# I2C_Switch_temp_sens.net
KiCad netlist of a schematic drawn in Altium Designer
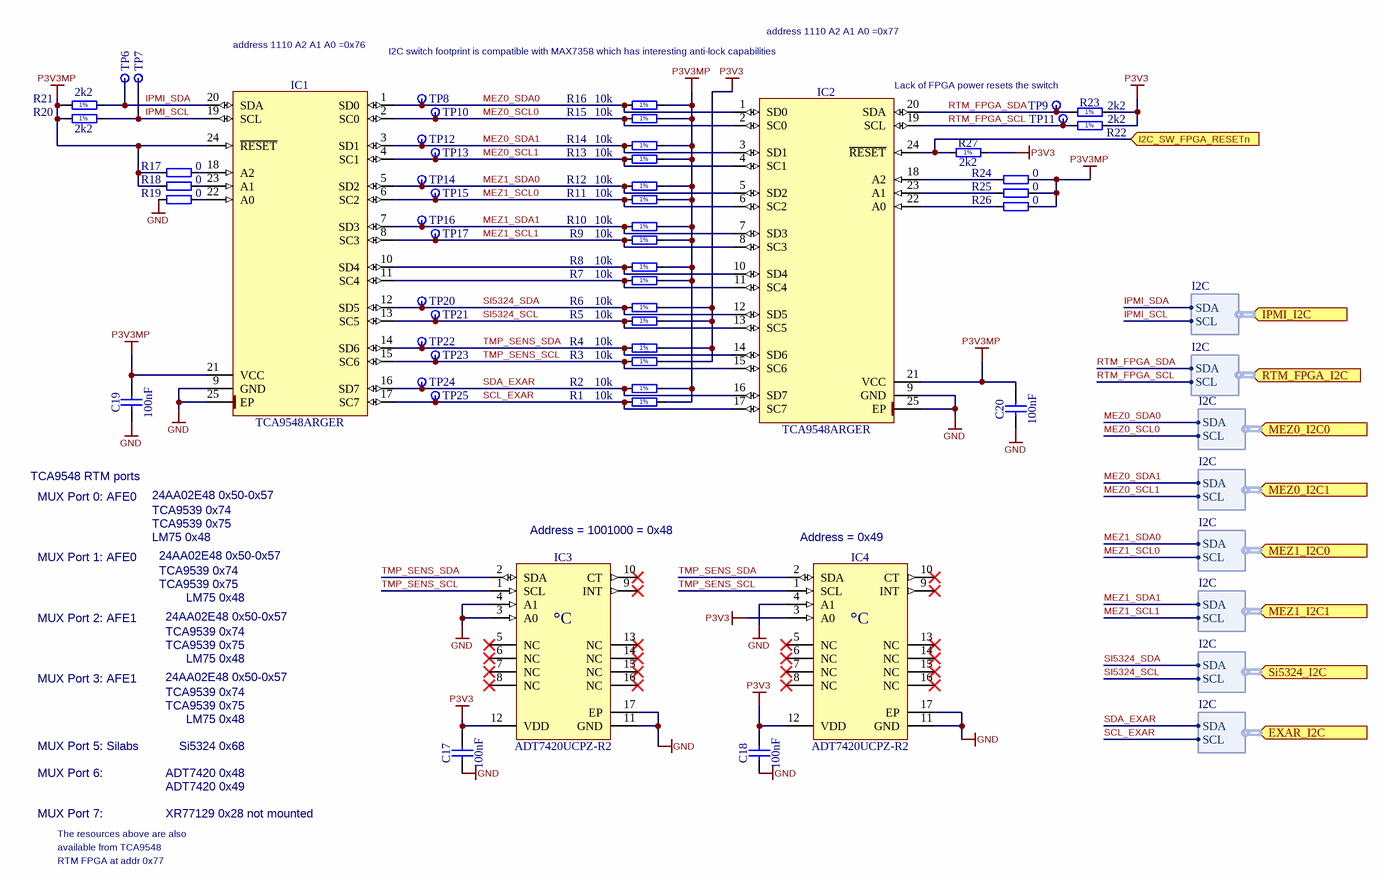
[diagram p0: I2C_Switch_temp_sens.SchDoc]

(export (version "E")
  (design (tool "Eeschema 10.0.6"))
  (components
    (comp (ref "C17")
      (value "100nF")
      (footprint "CAPC0603X33N")
      (description "Non-polarised capacitor")
      (fields
        (field (name "MANUFACTURER PART NUMBER") "CC0201_100NF_6.3V_10%_X5R")
        (field (name "MANUFACTURER") "GENERIC")
        (field (name "AUTHOR") "CERN DEM JLC")
      )
      (libsource (lib "Capacitors") (part "Capacitor - non polarized"))
    )
    (comp (ref "C18")
      (value "100nF")
      (footprint "CAPC0603X33N")
      (description "Non-polarised capacitor")
      (fields
        (field (name "MANUFACTURER PART NUMBER") "CC0201_100NF_6.3V_10%_X5R")
        (field (name "MANUFACTURER") "GENERIC")
        (field (name "AUTHOR") "CERN DEM JLC")
      )
      (libsource (lib "Capacitors") (part "Capacitor - non polarized"))
    )
    (comp (ref "C19")
      (value "100nF")
      (footprint "CAPC0603X33N")
      (description "Non-polarised capacitor")
      (fields
        (field (name "MANUFACTURER PART NUMBER") "CC0201_100NF_6.3V_10%_X5R")
        (field (name "MANUFACTURER") "GENERIC")
        (field (name "AUTHOR") "CERN DEM JLC")
      )
      (libsource (lib "Capacitors") (part "Capacitor - non polarized"))
    )
    (comp (ref "C20")
      (value "100nF")
      (footprint "CAPC0603X33N")
      (description "Non-polarised capacitor")
      (fields
        (field (name "MANUFACTURER PART NUMBER") "CC0201_100NF_6.3V_10%_X5R")
        (field (name "MANUFACTURER") "GENERIC")
        (field (name "AUTHOR") "CERN DEM JLC")
      )
      (libsource (lib "Capacitors") (part "Capacitor - non polarized"))
    )
    (comp (ref "IC1")
      (value "TCA9548ARGER")
      (footprint "QFN50P400X400X100-25N-S220")
      (description "Low Voltage 8-Channel I2C Switch With Reset")
      (fields (field (name "MANUFACTURER") "TEXAS INSTRUMENTS") (field (name "AUTHOR") "CERN DEM JLC"))
      (libsource (lib "ICs And Semiconductors") (part "TCA9548ARGER"))
    )
    (comp (ref "IC2")
      (value "TCA9548ARGER")
      (footprint "QFN50P400X400X100-25N-S220")
      (description "Low Voltage 8-Channel I2C Switch With Reset")
      (fields (field (name "MANUFACTURER") "TEXAS INSTRUMENTS") (field (name "AUTHOR") "CERN DEM JLC"))
      (libsource (lib "") (part "TCA9548ARGER_1"))
    )
    (comp (ref "IC3")
      (value "ADT7420UCPZ-R2")
      (footprint "QFN65P400X400X80-17N-S270")
      (description "±0.25°C Accurate, 16-Bit Digital I2C Temperature Sensor")
      (fields (field (name "MANUFACTURER") "ANALOG DEVICES") (field (name "AUTHOR") "CERN DEM JLC"))
      (libsource (lib "ICs And Semiconductors") (part "ADT7420"))
    )
    (comp (ref "IC4")
      (value "ADT7420UCPZ-R2")
      (footprint "QFN65P400X400X80-17N-S270")
      (description "±0.25°C Accurate, 16-Bit Digital I2C Temperature Sensor")
      (fields (field (name "MANUFACTURER") "ANALOG DEVICES") (field (name "AUTHOR") "CERN DEM JLC"))
      (libsource (lib "ICs And Semiconductors") (part "ADT7420"))
    )
    (comp (ref "R1")
      (value "10k")
      (footprint "RESC1005X40N")
      (description "Resistor - 1%")
      (fields
        (field (name "MANUFACTURER PART NUMBER") "R0402_10K_1%_0.0625W_100PPM")
        (field (name "MANUFACTURER") "GENERIC")
        (field (name "AUTHOR") "CERN DEM JLC")
      )
      (libsource (lib "Resistors") (part "Resistor - 1%"))
    )
    (comp (ref "R2")
      (value "10k")
      (footprint "RESC1005X40N")
      (description "Resistor - 1%")
      (fields
        (field (name "MANUFACTURER PART NUMBER") "R0402_10K_1%_0.0625W_100PPM")
        (field (name "MANUFACTURER") "GENERIC")
        (field (name "AUTHOR") "CERN DEM JLC")
      )
      (libsource (lib "Resistors") (part "Resistor - 1%"))
    )
    (comp (ref "R3")
      (value "10k")
      (footprint "RESC1005X40N")
      (description "Resistor - 1%")
      (fields
        (field (name "MANUFACTURER PART NUMBER") "R0402_10K_1%_0.0625W_100PPM")
        (field (name "MANUFACTURER") "GENERIC")
        (field (name "AUTHOR") "CERN DEM JLC")
      )
      (libsource (lib "Resistors") (part "Resistor - 1%"))
    )
    (comp (ref "R4")
      (value "10k")
      (footprint "RESC1005X40N")
      (description "Resistor - 1%")
      (fields
        (field (name "MANUFACTURER PART NUMBER") "R0402_10K_1%_0.0625W_100PPM")
        (field (name "MANUFACTURER") "GENERIC")
        (field (name "AUTHOR") "CERN DEM JLC")
      )
      (libsource (lib "Resistors") (part "Resistor - 1%"))
    )
    (comp (ref "R5")
      (value "10k")
      (footprint "RESC1005X40N")
      (description "Resistor - 1%")
      (fields
        (field (name "MANUFACTURER PART NUMBER") "R0402_10K_1%_0.0625W_100PPM")
        (field (name "MANUFACTURER") "GENERIC")
        (field (name "AUTHOR") "CERN DEM JLC")
      )
      (libsource (lib "Resistors") (part "Resistor - 1%"))
    )
    (comp (ref "R6")
      (value "10k")
      (footprint "RESC1005X40N")
      (description "Resistor - 1%")
      (fields
        (field (name "MANUFACTURER PART NUMBER") "R0402_10K_1%_0.0625W_100PPM")
        (field (name "MANUFACTURER") "GENERIC")
        (field (name "AUTHOR") "CERN DEM JLC")
      )
      (libsource (lib "Resistors") (part "Resistor - 1%"))
    )
    (comp (ref "R7")
      (value "10k")
      (footprint "RESC1005X40N")
      (description "Resistor - 1%")
      (fields
        (field (name "MANUFACTURER PART NUMBER") "R0402_10K_1%_0.0625W_100PPM")
        (field (name "MANUFACTURER") "GENERIC")
        (field (name "AUTHOR") "CERN DEM JLC")
      )
      (libsource (lib "Resistors") (part "Resistor - 1%"))
    )
    (comp (ref "R8")
      (value "10k")
      (footprint "RESC1005X40N")
      (description "Resistor - 1%")
      (fields
        (field (name "MANUFACTURER PART NUMBER") "R0402_10K_1%_0.0625W_100PPM")
        (field (name "MANUFACTURER") "GENERIC")
        (field (name "AUTHOR") "CERN DEM JLC")
      )
      (libsource (lib "Resistors") (part "Resistor - 1%"))
    )
    (comp (ref "R9")
      (value "10k")
      (footprint "RESC1005X40N")
      (description "Resistor - 1%")
      (fields
        (field (name "MANUFACTURER PART NUMBER") "R0402_10K_1%_0.0625W_100PPM")
        (field (name "MANUFACTURER") "GENERIC")
        (field (name "AUTHOR") "CERN DEM JLC")
      )
      (libsource (lib "Resistors") (part "Resistor - 1%"))
    )
    (comp (ref "R10")
      (value "10k")
      (footprint "RESC1005X40N")
      (description "Resistor - 1%")
      (fields
        (field (name "MANUFACTURER PART NUMBER") "R0402_10K_1%_0.0625W_100PPM")
        (field (name "MANUFACTURER") "GENERIC")
        (field (name "AUTHOR") "CERN DEM JLC")
      )
      (libsource (lib "Resistors") (part "Resistor - 1%"))
    )
    (comp (ref "R11")
      (value "10k")
      (footprint "RESC1005X40N")
      (description "Resistor - 1%")
      (fields
        (field (name "MANUFACTURER PART NUMBER") "R0402_10K_1%_0.0625W_100PPM")
        (field (name "MANUFACTURER") "GENERIC")
        (field (name "AUTHOR") "CERN DEM JLC")
      )
      (libsource (lib "Resistors") (part "Resistor - 1%"))
    )
    (comp (ref "R12")
      (value "10k")
      (footprint "RESC1005X40N")
      (description "Resistor - 1%")
      (fields
        (field (name "MANUFACTURER PART NUMBER") "R0402_10K_1%_0.0625W_100PPM")
        (field (name "MANUFACTURER") "GENERIC")
        (field (name "AUTHOR") "CERN DEM JLC")
      )
      (libsource (lib "Resistors") (part "Resistor - 1%"))
    )
    (comp (ref "R13")
      (value "10k")
      (footprint "RESC1005X40N")
      (description "Resistor - 1%")
      (fields
        (field (name "MANUFACTURER PART NUMBER") "R0402_10K_1%_0.0625W_100PPM")
        (field (name "MANUFACTURER") "GENERIC")
        (field (name "AUTHOR") "CERN DEM JLC")
      )
      (libsource (lib "Resistors") (part "Resistor - 1%"))
    )
    (comp (ref "R14")
      (value "10k")
      (footprint "RESC1005X40N")
      (description "Resistor - 1%")
      (fields
        (field (name "MANUFACTURER PART NUMBER") "R0402_10K_1%_0.0625W_100PPM")
        (field (name "MANUFACTURER") "GENERIC")
        (field (name "AUTHOR") "CERN DEM JLC")
      )
      (libsource (lib "Resistors") (part "Resistor - 1%"))
    )
    (comp (ref "R15")
      (value "10k")
      (footprint "RESC1005X40N")
      (description "Resistor - 1%")
      (fields
        (field (name "MANUFACTURER PART NUMBER") "R0402_10K_1%_0.0625W_100PPM")
        (field (name "MANUFACTURER") "GENERIC")
        (field (name "AUTHOR") "CERN DEM JLC")
      )
      (libsource (lib "Resistors") (part "Resistor - 1%"))
    )
    (comp (ref "R16")
      (value "10k")
      (footprint "RESC1005X40N")
      (description "Resistor - 1%")
      (fields
        (field (name "MANUFACTURER PART NUMBER") "R0402_10K_1%_0.0625W_100PPM")
        (field (name "MANUFACTURER") "GENERIC")
        (field (name "AUTHOR") "CERN DEM JLC")
      )
      (libsource (lib "Resistors") (part "Resistor - 1%"))
    )
    (comp (ref "R17")
      (value "0")
      (footprint "RESC1005X40N")
      (description "Resistor")
      (fields
        (field (name "MANUFACTURER PART NUMBER") "R0402_0R_JUMPER")
        (field (name "MANUFACTURER") "GENERIC")
        (field (name "AUTHOR") "CERN DEM JLC")
      )
      (libsource (lib "Resistors") (part "Resistor"))
    )
    (comp (ref "R18")
      (value "0")
      (footprint "RESC1005X40N")
      (description "Resistor")
      (fields
        (field (name "MANUFACTURER PART NUMBER") "R0402_0R_JUMPER")
        (field (name "MANUFACTURER") "GENERIC")
        (field (name "AUTHOR") "CERN DEM JLC")
      )
      (libsource (lib "Resistors") (part "Resistor"))
    )
    (comp (ref "R19")
      (value "0")
      (footprint "RESC1005X40N")
      (description "Resistor")
      (fields
        (field (name "MANUFACTURER PART NUMBER") "R0402_0R_JUMPER")
        (field (name "MANUFACTURER") "GENERIC")
        (field (name "AUTHOR") "CERN DEM JLC")
      )
      (libsource (lib "Resistors") (part "Resistor"))
    )
    (comp (ref "R20")
      (value "2k2")
      (footprint "RESC1005X40N")
      (description "Resistor - 1%")
      (fields
        (field (name "MANUFACTURER PART NUMBER") "R0402_2K2_1%_0.0625W_100PPM")
        (field (name "MANUFACTURER") "GENERIC")
        (field (name "AUTHOR") "CERN DEM JLC")
      )
      (libsource (lib "Resistors") (part "Resistor - 1%"))
    )
    (comp (ref "R21")
      (value "2k2")
      (footprint "RESC1005X40N")
      (description "Resistor - 1%")
      (fields
        (field (name "MANUFACTURER PART NUMBER") "R0402_2K2_1%_0.0625W_100PPM")
        (field (name "MANUFACTURER") "GENERIC")
        (field (name "AUTHOR") "CERN DEM JLC")
      )
      (libsource (lib "Resistors") (part "Resistor - 1%"))
    )
    (comp (ref "R22")
      (value "2k2")
      (footprint "RESC1005X40N")
      (description "Resistor - 1%")
      (fields
        (field (name "MANUFACTURER PART NUMBER") "R0402_2K2_1%_0.0625W_100PPM")
        (field (name "MANUFACTURER") "GENERIC")
        (field (name "AUTHOR") "CERN DEM JLC")
      )
      (libsource (lib "Resistors") (part "Resistor - 1%"))
    )
    (comp (ref "R23")
      (value "2k2")
      (footprint "RESC1005X40N")
      (description "Resistor - 1%")
      (fields
        (field (name "MANUFACTURER PART NUMBER") "R0402_2K2_1%_0.0625W_100PPM")
        (field (name "MANUFACTURER") "GENERIC")
        (field (name "AUTHOR") "CERN DEM JLC")
      )
      (libsource (lib "Resistors") (part "Resistor - 1%"))
    )
    (comp (ref "R24")
      (value "0")
      (footprint "RESC1005X40N")
      (description "Resistor")
      (fields
        (field (name "MANUFACTURER PART NUMBER") "R0402_0R_JUMPER")
        (field (name "MANUFACTURER") "GENERIC")
        (field (name "AUTHOR") "CERN DEM JLC")
      )
      (libsource (lib "Resistors") (part "Resistor"))
    )
    (comp (ref "R25")
      (value "0")
      (footprint "RESC1005X40N")
      (description "Resistor")
      (fields
        (field (name "MANUFACTURER PART NUMBER") "R0402_0R_JUMPER")
        (field (name "MANUFACTURER") "GENERIC")
        (field (name "AUTHOR") "CERN DEM JLC")
      )
      (libsource (lib "Resistors") (part "Resistor"))
    )
    (comp (ref "R26")
      (value "0")
      (footprint "RESC1005X40N")
      (description "Resistor")
      (fields
        (field (name "MANUFACTURER PART NUMBER") "R0402_0R_JUMPER")
        (field (name "MANUFACTURER") "GENERIC")
        (field (name "AUTHOR") "CERN DEM JLC")
      )
      (libsource (lib "Resistors") (part "Resistor"))
    )
    (comp (ref "R27")
      (value "2k2")
      (footprint "RESC1005X40N")
      (description "Resistor - 1%")
      (fields
        (field (name "MANUFACTURER PART NUMBER") "R0402_2K2_1%_0.0625W_100PPM")
        (field (name "MANUFACTURER") "GENERIC")
        (field (name "AUTHOR") "CERN DEM JLC")
      )
      (libsource (lib "Resistors") (part "Resistor - 1%"))
    )
    (comp (ref "TP6")
      (value "Test Point")
      (footprint "TPS127")
      (fields (field (name "PART NUMBER") "SMD_PAD_1.27X1.27MM") (field (name "AUTHOR") "CERN DEM JLC"))
      (libsource (lib "Eletro-mechanical") (part "Test Point"))
    )
    (comp (ref "TP7")
      (value "Test Point")
      (footprint "TPS127")
      (fields (field (name "PART NUMBER") "SMD_PAD_1.27X1.27MM") (field (name "AUTHOR") "CERN DEM JLC"))
      (libsource (lib "Eletro-mechanical") (part "Test Point"))
    )
    (comp (ref "TP8")
      (value "Test Point")
      (footprint "TPS127")
      (fields (field (name "PART NUMBER") "SMD_PAD_1.27X1.27MM") (field (name "AUTHOR") "CERN DEM JLC"))
      (libsource (lib "Eletro-mechanical") (part "Test Point"))
    )
    (comp (ref "TP9")
      (value "Test Point")
      (footprint "TPS127")
      (fields (field (name "PART NUMBER") "SMD_PAD_1.27X1.27MM") (field (name "AUTHOR") "CERN DEM JLC"))
      (libsource (lib "Eletro-mechanical") (part "Test Point"))
    )
    (comp (ref "TP10")
      (value "Test Point")
      (footprint "TPS127")
      (fields (field (name "PART NUMBER") "SMD_PAD_1.27X1.27MM") (field (name "AUTHOR") "CERN DEM JLC"))
      (libsource (lib "Eletro-mechanical") (part "Test Point"))
    )
    (comp (ref "TP11")
      (value "Test Point")
      (footprint "TPS127")
      (fields (field (name "PART NUMBER") "SMD_PAD_1.27X1.27MM") (field (name "AUTHOR") "CERN DEM JLC"))
      (libsource (lib "Eletro-mechanical") (part "Test Point"))
    )
    (comp (ref "TP12")
      (value "Test Point")
      (footprint "TPS127")
      (fields (field (name "PART NUMBER") "SMD_PAD_1.27X1.27MM") (field (name "AUTHOR") "CERN DEM JLC"))
      (libsource (lib "Eletro-mechanical") (part "Test Point"))
    )
    (comp (ref "TP13")
      (value "Test Point")
      (footprint "TPS127")
      (fields (field (name "PART NUMBER") "SMD_PAD_1.27X1.27MM") (field (name "AUTHOR") "CERN DEM JLC"))
      (libsource (lib "Eletro-mechanical") (part "Test Point"))
    )
    (comp (ref "TP14")
      (value "Test Point")
      (footprint "TPS127")
      (fields (field (name "PART NUMBER") "SMD_PAD_1.27X1.27MM") (field (name "AUTHOR") "CERN DEM JLC"))
      (libsource (lib "Eletro-mechanical") (part "Test Point"))
    )
    (comp (ref "TP15")
      (value "Test Point")
      (footprint "TPS127")
      (fields (field (name "PART NUMBER") "SMD_PAD_1.27X1.27MM") (field (name "AUTHOR") "CERN DEM JLC"))
      (libsource (lib "Eletro-mechanical") (part "Test Point"))
    )
    (comp (ref "TP16")
      (value "Test Point")
      (footprint "TPS127")
      (fields (field (name "PART NUMBER") "SMD_PAD_1.27X1.27MM") (field (name "AUTHOR") "CERN DEM JLC"))
      (libsource (lib "Eletro-mechanical") (part "Test Point"))
    )
    (comp (ref "TP17")
      (value "Test Point")
      (footprint "TPS127")
      (fields (field (name "PART NUMBER") "SMD_PAD_1.27X1.27MM") (field (name "AUTHOR") "CERN DEM JLC"))
      (libsource (lib "Eletro-mechanical") (part "Test Point"))
    )
    (comp (ref "TP20")
      (value "Test Point")
      (footprint "TPS127")
      (fields (field (name "PART NUMBER") "SMD_PAD_1.27X1.27MM") (field (name "AUTHOR") "CERN DEM JLC"))
      (libsource (lib "Eletro-mechanical") (part "Test Point"))
    )
    (comp (ref "TP21")
      (value "Test Point")
      (footprint "TPS127")
      (fields (field (name "PART NUMBER") "SMD_PAD_1.27X1.27MM") (field (name "AUTHOR") "CERN DEM JLC"))
      (libsource (lib "Eletro-mechanical") (part "Test Point"))
    )
    (comp (ref "TP22")
      (value "Test Point")
      (footprint "TPS127")
      (fields (field (name "PART NUMBER") "SMD_PAD_1.27X1.27MM") (field (name "AUTHOR") "CERN DEM JLC"))
      (libsource (lib "Eletro-mechanical") (part "Test Point"))
    )
    (comp (ref "TP23")
      (value "Test Point")
      (footprint "TPS127")
      (fields (field (name "PART NUMBER") "SMD_PAD_1.27X1.27MM") (field (name "AUTHOR") "CERN DEM JLC"))
      (libsource (lib "Eletro-mechanical") (part "Test Point"))
    )
    (comp (ref "TP24")
      (value "Test Point")
      (footprint "TPS127")
      (fields (field (name "PART NUMBER") "SMD_PAD_1.27X1.27MM") (field (name "AUTHOR") "CERN DEM JLC"))
      (libsource (lib "Eletro-mechanical") (part "Test Point"))
    )
    (comp (ref "TP25")
      (value "Test Point")
      (footprint "TPS127")
      (fields (field (name "PART NUMBER") "SMD_PAD_1.27X1.27MM") (field (name "AUTHOR") "CERN DEM JLC"))
      (libsource (lib "Eletro-mechanical") (part "Test Point"))
    )
  )
  (nets
    (net (code "2") (name "/I2C_SW_FPGA_RESETn") (class "Default")
      (node (ref "IC2") (pin "24") (pinfunction "~{RESET}_24") (pintype "input"))
      (node (ref "R27") (pin "1") (pinfunction "1_1") (pintype "passive"))
    )
    (net (code "3") (name "/IPMI_SCL") (class "Default")
      (node (ref "IC1") (pin "19") (pinfunction "SCL_19") (pintype "bidirectional"))
      (node (ref "R20") (pin "2") (pinfunction "2_2") (pintype "passive"))
      (node (ref "TP7") (pin "1") (pinfunction "1_1") (pintype "bidirectional"))
    )
    (net (code "4") (name "/IPMI_SDA") (class "Default")
      (node (ref "IC1") (pin "20") (pinfunction "SDA_20") (pintype "bidirectional"))
      (node (ref "R21") (pin "2") (pinfunction "2_2") (pintype "passive"))
      (node (ref "TP6") (pin "1") (pinfunction "1_1") (pintype "bidirectional"))
    )
    (net (code "5") (name "/MEZ0_SCL0") (class "Default")
      (node (ref "IC1") (pin "2") (pinfunction "SC0_2") (pintype "bidirectional"))
      (node (ref "IC2") (pin "2") (pinfunction "SC0_2") (pintype "bidirectional"))
      (node (ref "R15") (pin "1") (pinfunction "1_1") (pintype "passive"))
      (node (ref "TP10") (pin "1") (pinfunction "1_1") (pintype "bidirectional"))
    )
    (net (code "6") (name "/MEZ0_SCL1") (class "Default")
      (node (ref "IC1") (pin "4") (pinfunction "SC1_4") (pintype "bidirectional"))
      (node (ref "IC2") (pin "4") (pinfunction "SC1_4") (pintype "bidirectional"))
      (node (ref "R13") (pin "1") (pinfunction "1_1") (pintype "passive"))
      (node (ref "TP13") (pin "1") (pinfunction "1_1") (pintype "bidirectional"))
    )
    (net (code "7") (name "/MEZ0_SDA0") (class "Default")
      (node (ref "IC1") (pin "1") (pinfunction "SD0_1") (pintype "bidirectional"))
      (node (ref "IC2") (pin "1") (pinfunction "SD0_1") (pintype "bidirectional"))
      (node (ref "R16") (pin "1") (pinfunction "1_1") (pintype "passive"))
      (node (ref "TP8") (pin "1") (pinfunction "1_1") (pintype "bidirectional"))
    )
    (net (code "8") (name "/MEZ0_SDA1") (class "Default")
      (node (ref "IC1") (pin "3") (pinfunction "SD1_3") (pintype "bidirectional"))
      (node (ref "IC2") (pin "3") (pinfunction "SD1_3") (pintype "bidirectional"))
      (node (ref "R14") (pin "1") (pinfunction "1_1") (pintype "passive"))
      (node (ref "TP12") (pin "1") (pinfunction "1_1") (pintype "bidirectional"))
    )
    (net (code "9") (name "/MEZ1_SCL0") (class "Default")
      (node (ref "IC1") (pin "6") (pinfunction "SC2_6") (pintype "bidirectional"))
      (node (ref "IC2") (pin "6") (pinfunction "SC2_6") (pintype "bidirectional"))
      (node (ref "R11") (pin "1") (pinfunction "1_1") (pintype "passive"))
      (node (ref "TP15") (pin "1") (pinfunction "1_1") (pintype "bidirectional"))
    )
    (net (code "10") (name "/MEZ1_SCL1") (class "Default")
      (node (ref "IC1") (pin "8") (pinfunction "SC3_8") (pintype "bidirectional"))
      (node (ref "IC2") (pin "8") (pinfunction "SC3_8") (pintype "bidirectional"))
      (node (ref "R9") (pin "1") (pinfunction "1_1") (pintype "passive"))
      (node (ref "TP17") (pin "1") (pinfunction "1_1") (pintype "bidirectional"))
    )
    (net (code "11") (name "/MEZ1_SDA0") (class "Default")
      (node (ref "IC1") (pin "5") (pinfunction "SD2_5") (pintype "bidirectional"))
      (node (ref "IC2") (pin "5") (pinfunction "SD2_5") (pintype "bidirectional"))
      (node (ref "R12") (pin "1") (pinfunction "1_1") (pintype "passive"))
      (node (ref "TP14") (pin "1") (pinfunction "1_1") (pintype "bidirectional"))
    )
    (net (code "12") (name "/MEZ1_SDA1") (class "Default")
      (node (ref "IC1") (pin "7") (pinfunction "SD3_7") (pintype "bidirectional"))
      (node (ref "IC2") (pin "7") (pinfunction "SD3_7") (pintype "bidirectional"))
      (node (ref "R10") (pin "1") (pinfunction "1_1") (pintype "passive"))
      (node (ref "TP16") (pin "1") (pinfunction "1_1") (pintype "bidirectional"))
    )
    (net (code "13") (name "/RTM_FPGA_SCL") (class "Default")
      (node (ref "IC2") (pin "19") (pinfunction "SCL_19") (pintype "bidirectional"))
      (node (ref "R22") (pin "1") (pinfunction "1_1") (pintype "passive"))
      (node (ref "TP11") (pin "1") (pinfunction "1_1") (pintype "bidirectional"))
    )
    (net (code "14") (name "/RTM_FPGA_SDA") (class "Default")
      (node (ref "IC2") (pin "20") (pinfunction "SDA_20") (pintype "bidirectional"))
      (node (ref "R23") (pin "1") (pinfunction "1_1") (pintype "passive"))
      (node (ref "TP9") (pin "1") (pinfunction "1_1") (pintype "bidirectional"))
    )
    (net (code "15") (name "/SCL_EXAR") (class "Default")
      (node (ref "IC1") (pin "17") (pinfunction "SC7_17") (pintype "bidirectional"))
      (node (ref "IC2") (pin "17") (pinfunction "SC7_17") (pintype "bidirectional"))
      (node (ref "R1") (pin "1") (pinfunction "1_1") (pintype "passive"))
      (node (ref "TP25") (pin "1") (pinfunction "1_1") (pintype "bidirectional"))
    )
    (net (code "16") (name "/SDA_EXAR") (class "Default")
      (node (ref "IC1") (pin "16") (pinfunction "SD7_16") (pintype "bidirectional"))
      (node (ref "IC2") (pin "16") (pinfunction "SD7_16") (pintype "bidirectional"))
      (node (ref "R2") (pin "1") (pinfunction "1_1") (pintype "passive"))
      (node (ref "TP24") (pin "1") (pinfunction "1_1") (pintype "bidirectional"))
    )
    (net (code "17") (name "/SI5324_SCL") (class "Default")
      (node (ref "IC1") (pin "13") (pinfunction "SC5_13") (pintype "bidirectional"))
      (node (ref "IC2") (pin "13") (pinfunction "SC5_13") (pintype "bidirectional"))
      (node (ref "R5") (pin "1") (pinfunction "1_1") (pintype "passive"))
      (node (ref "TP21") (pin "1") (pinfunction "1_1") (pintype "bidirectional"))
    )
    (net (code "18") (name "/SI5324_SDA") (class "Default")
      (node (ref "IC1") (pin "12") (pinfunction "SD5_12") (pintype "bidirectional"))
      (node (ref "IC2") (pin "12") (pinfunction "SD5_12") (pintype "bidirectional"))
      (node (ref "R6") (pin "1") (pinfunction "1_1") (pintype "passive"))
      (node (ref "TP20") (pin "1") (pinfunction "1_1") (pintype "bidirectional"))
    )
    (net (code "19") (name "/TMP_SENS_SCL") (class "Default")
      (node (ref "IC1") (pin "15") (pinfunction "SC6_15") (pintype "bidirectional"))
      (node (ref "IC2") (pin "15") (pinfunction "SC6_15") (pintype "bidirectional"))
      (node (ref "IC3") (pin "1") (pinfunction "SCL_1") (pintype "input"))
      (node (ref "IC4") (pin "1") (pinfunction "SCL_1") (pintype "input"))
      (node (ref "R3") (pin "1") (pinfunction "1_1") (pintype "passive"))
      (node (ref "TP23") (pin "1") (pinfunction "1_1") (pintype "bidirectional"))
    )
    (net (code "20") (name "/TMP_SENS_SDA") (class "Default")
      (node (ref "IC1") (pin "14") (pinfunction "SD6_14") (pintype "bidirectional"))
      (node (ref "IC2") (pin "14") (pinfunction "SD6_14") (pintype "bidirectional"))
      (node (ref "IC3") (pin "2") (pinfunction "SDA_2") (pintype "bidirectional"))
      (node (ref "IC4") (pin "2") (pinfunction "SDA_2") (pintype "bidirectional"))
      (node (ref "R4") (pin "1") (pinfunction "1_1") (pintype "passive"))
      (node (ref "TP22") (pin "1") (pinfunction "1_1") (pintype "bidirectional"))
    )
    (net (code "22") (name "GND") (class "Default")
      (node (ref "C17") (pin "1") (pinfunction "1_1") (pintype "passive"))
      (node (ref "C18") (pin "1") (pinfunction "1_1") (pintype "passive"))
      (node (ref "C19") (pin "1") (pinfunction "1_1") (pintype "passive"))
      (node (ref "C20") (pin "1") (pinfunction "1_1") (pintype "passive"))
      (node (ref "IC1") (pin "25") (pinfunction "EP_25") (pintype "power_in"))
      (node (ref "IC1") (pin "9") (pinfunction "GND_9") (pintype "power_in"))
      (node (ref "IC2") (pin "25") (pinfunction "EP_25") (pintype "power_in"))
      (node (ref "IC2") (pin "9") (pinfunction "GND_9") (pintype "power_in"))
      (node (ref "IC3") (pin "11") (pinfunction "GND_11") (pintype "power_in"))
      (node (ref "IC3") (pin "17") (pinfunction "EP_17") (pintype "power_in"))
      (node (ref "IC3") (pin "3") (pinfunction "A0_3") (pintype "input"))
      (node (ref "IC3") (pin "4") (pinfunction "A1_4") (pintype "input"))
      (node (ref "IC4") (pin "11") (pinfunction "GND_11") (pintype "power_in"))
      (node (ref "IC4") (pin "17") (pinfunction "EP_17") (pintype "power_in"))
      (node (ref "IC4") (pin "4") (pinfunction "A1_4") (pintype "input"))
      (node (ref "R19") (pin "1") (pinfunction "1_1") (pintype "passive"))
    )
    (net (code "23") (name "Net-(IC1-A0)") (class "Default")
      (node (ref "IC1") (pin "22") (pinfunction "A0_22") (pintype "input"))
      (node (ref "R19") (pin "2") (pinfunction "2_2") (pintype "passive"))
    )
    (net (code "24") (name "Net-(IC1-A1)") (class "Default")
      (node (ref "IC1") (pin "23") (pinfunction "A1_23") (pintype "input"))
      (node (ref "R18") (pin "2") (pinfunction "2_2") (pintype "passive"))
    )
    (net (code "25") (name "Net-(IC1-A2)") (class "Default")
      (node (ref "IC1") (pin "18") (pinfunction "A2_18") (pintype "input"))
      (node (ref "R17") (pin "2") (pinfunction "2_2") (pintype "passive"))
    )
    (net (code "26") (name "Net-(IC1-SC4)") (class "Default")
      (node (ref "IC1") (pin "11") (pinfunction "SC4_11") (pintype "bidirectional"))
      (node (ref "IC2") (pin "11") (pinfunction "SC4_11") (pintype "bidirectional"))
      (node (ref "R7") (pin "1") (pinfunction "1_1") (pintype "passive"))
    )
    (net (code "27") (name "Net-(IC1-SD4)") (class "Default")
      (node (ref "IC1") (pin "10") (pinfunction "SD4_10") (pintype "bidirectional"))
      (node (ref "IC2") (pin "10") (pinfunction "SD4_10") (pintype "bidirectional"))
      (node (ref "R8") (pin "1") (pinfunction "1_1") (pintype "passive"))
    )
    (net (code "28") (name "Net-(IC2-A0)") (class "Default")
      (node (ref "IC2") (pin "22") (pinfunction "A0_22") (pintype "input"))
      (node (ref "R26") (pin "1") (pinfunction "1_1") (pintype "passive"))
    )
    (net (code "29") (name "Net-(IC2-A1)") (class "Default")
      (node (ref "IC2") (pin "23") (pinfunction "A1_23") (pintype "input"))
      (node (ref "R25") (pin "1") (pinfunction "1_1") (pintype "passive"))
    )
    (net (code "30") (name "Net-(IC2-A2)") (class "Default")
      (node (ref "IC2") (pin "18") (pinfunction "A2_18") (pintype "input"))
      (node (ref "R24") (pin "1") (pinfunction "1_1") (pintype "passive"))
    )
    (net (code "31") (name "P3V3") (class "Default")
      (node (ref "C17") (pin "2") (pinfunction "2_2") (pintype "passive"))
      (node (ref "C18") (pin "2") (pinfunction "2_2") (pintype "passive"))
      (node (ref "IC3") (pin "12") (pinfunction "VDD_12") (pintype "power_in"))
      (node (ref "IC4") (pin "12") (pinfunction "VDD_12") (pintype "power_in"))
      (node (ref "IC4") (pin "3") (pinfunction "A0_3") (pintype "input"))
      (node (ref "R22") (pin "2") (pinfunction "2_2") (pintype "passive"))
      (node (ref "R23") (pin "2") (pinfunction "2_2") (pintype "passive"))
      (node (ref "R27") (pin "2") (pinfunction "2_2") (pintype "passive"))
      (node (ref "R3") (pin "2") (pinfunction "2_2") (pintype "passive"))
      (node (ref "R4") (pin "2") (pinfunction "2_2") (pintype "passive"))
      (node (ref "R5") (pin "2") (pinfunction "2_2") (pintype "passive"))
      (node (ref "R6") (pin "2") (pinfunction "2_2") (pintype "passive"))
    )
    (net (code "32") (name "P3V3MP") (class "Default")
      (node (ref "C19") (pin "2") (pinfunction "2_2") (pintype "passive"))
      (node (ref "C20") (pin "2") (pinfunction "2_2") (pintype "passive"))
      (node (ref "IC1") (pin "21") (pinfunction "VCC_21") (pintype "power_in"))
      (node (ref "IC1") (pin "24") (pinfunction "~{RESET}_24") (pintype "input"))
      (node (ref "IC2") (pin "21") (pinfunction "VCC_21") (pintype "power_in"))
      (node (ref "R1") (pin "2") (pinfunction "2_2") (pintype "passive"))
      (node (ref "R10") (pin "2") (pinfunction "2_2") (pintype "passive"))
      (node (ref "R11") (pin "2") (pinfunction "2_2") (pintype "passive"))
      (node (ref "R12") (pin "2") (pinfunction "2_2") (pintype "passive"))
      (node (ref "R13") (pin "2") (pinfunction "2_2") (pintype "passive"))
      (node (ref "R14") (pin "2") (pinfunction "2_2") (pintype "passive"))
      (node (ref "R15") (pin "2") (pinfunction "2_2") (pintype "passive"))
      (node (ref "R16") (pin "2") (pinfunction "2_2") (pintype "passive"))
      (node (ref "R17") (pin "1") (pinfunction "1_1") (pintype "passive"))
      (node (ref "R18") (pin "1") (pinfunction "1_1") (pintype "passive"))
      (node (ref "R2") (pin "2") (pinfunction "2_2") (pintype "passive"))
      (node (ref "R20") (pin "1") (pinfunction "1_1") (pintype "passive"))
      (node (ref "R21") (pin "1") (pinfunction "1_1") (pintype "passive"))
      (node (ref "R24") (pin "2") (pinfunction "2_2") (pintype "passive"))
      (node (ref "R25") (pin "2") (pinfunction "2_2") (pintype "passive"))
      (node (ref "R26") (pin "2") (pinfunction "2_2") (pintype "passive"))
      (node (ref "R7") (pin "2") (pinfunction "2_2") (pintype "passive"))
      (node (ref "R8") (pin "2") (pinfunction "2_2") (pintype "passive"))
      (node (ref "R9") (pin "2") (pinfunction "2_2") (pintype "passive"))
    )
    (net (code "33") (name "unconnected-(IC3-CT-Pad10)") (class "Default")
      (node (ref "IC3") (pin "10") (pinfunction "CT_10") (pintype "output+no_connect"))
    )
    (net (code "34") (name "unconnected-(IC3-INT-Pad9)") (class "Default")
      (node (ref "IC3") (pin "9") (pinfunction "INT_9") (pintype "output+no_connect"))
    )
    (net (code "35") (name "unconnected-(IC3-NC-Pad5)") (class "Default")
      (node (ref "IC3") (pin "5") (pinfunction "NC_5") (pintype "passive+no_connect"))
    )
    (net (code "36") (name "unconnected-(IC3-NC-Pad6)") (class "Default")
      (node (ref "IC3") (pin "6") (pinfunction "NC_6") (pintype "passive+no_connect"))
    )
    (net (code "37") (name "unconnected-(IC3-NC-Pad7)") (class "Default")
      (node (ref "IC3") (pin "7") (pinfunction "NC_7") (pintype "passive+no_connect"))
    )
    (net (code "38") (name "unconnected-(IC3-NC-Pad8)") (class "Default")
      (node (ref "IC3") (pin "8") (pinfunction "NC_8") (pintype "passive+no_connect"))
    )
    (net (code "39") (name "unconnected-(IC3-NC-Pad13)") (class "Default")
      (node (ref "IC3") (pin "13") (pinfunction "NC_13") (pintype "passive+no_connect"))
    )
    (net (code "40") (name "unconnected-(IC3-NC-Pad14)") (class "Default")
      (node (ref "IC3") (pin "14") (pinfunction "NC_14") (pintype "passive+no_connect"))
    )
    (net (code "41") (name "unconnected-(IC3-NC-Pad15)") (class "Default")
      (node (ref "IC3") (pin "15") (pinfunction "NC_15") (pintype "passive+no_connect"))
    )
    (net (code "42") (name "unconnected-(IC3-NC-Pad16)") (class "Default")
      (node (ref "IC3") (pin "16") (pinfunction "NC_16") (pintype "passive+no_connect"))
    )
    (net (code "43") (name "unconnected-(IC4-CT-Pad10)") (class "Default")
      (node (ref "IC4") (pin "10") (pinfunction "CT_10") (pintype "output+no_connect"))
    )
    (net (code "44") (name "unconnected-(IC4-INT-Pad9)") (class "Default")
      (node (ref "IC4") (pin "9") (pinfunction "INT_9") (pintype "output+no_connect"))
    )
    (net (code "45") (name "unconnected-(IC4-NC-Pad5)") (class "Default")
      (node (ref "IC4") (pin "5") (pinfunction "NC_5") (pintype "passive+no_connect"))
    )
    (net (code "46") (name "unconnected-(IC4-NC-Pad6)") (class "Default")
      (node (ref "IC4") (pin "6") (pinfunction "NC_6") (pintype "passive+no_connect"))
    )
    (net (code "47") (name "unconnected-(IC4-NC-Pad7)") (class "Default")
      (node (ref "IC4") (pin "7") (pinfunction "NC_7") (pintype "passive+no_connect"))
    )
    (net (code "48") (name "unconnected-(IC4-NC-Pad8)") (class "Default")
      (node (ref "IC4") (pin "8") (pinfunction "NC_8") (pintype "passive+no_connect"))
    )
    (net (code "49") (name "unconnected-(IC4-NC-Pad13)") (class "Default")
      (node (ref "IC4") (pin "13") (pinfunction "NC_13") (pintype "passive+no_connect"))
    )
    (net (code "50") (name "unconnected-(IC4-NC-Pad14)") (class "Default")
      (node (ref "IC4") (pin "14") (pinfunction "NC_14") (pintype "passive+no_connect"))
    )
    (net (code "51") (name "unconnected-(IC4-NC-Pad15)") (class "Default")
      (node (ref "IC4") (pin "15") (pinfunction "NC_15") (pintype "passive+no_connect"))
    )
    (net (code "52") (name "unconnected-(IC4-NC-Pad16)") (class "Default")
      (node (ref "IC4") (pin "16") (pinfunction "NC_16") (pintype "passive+no_connect"))
    )
  )
)
